# PilotPi_Power.net
KiCad netlist of a schematic drawn in Altium Designer
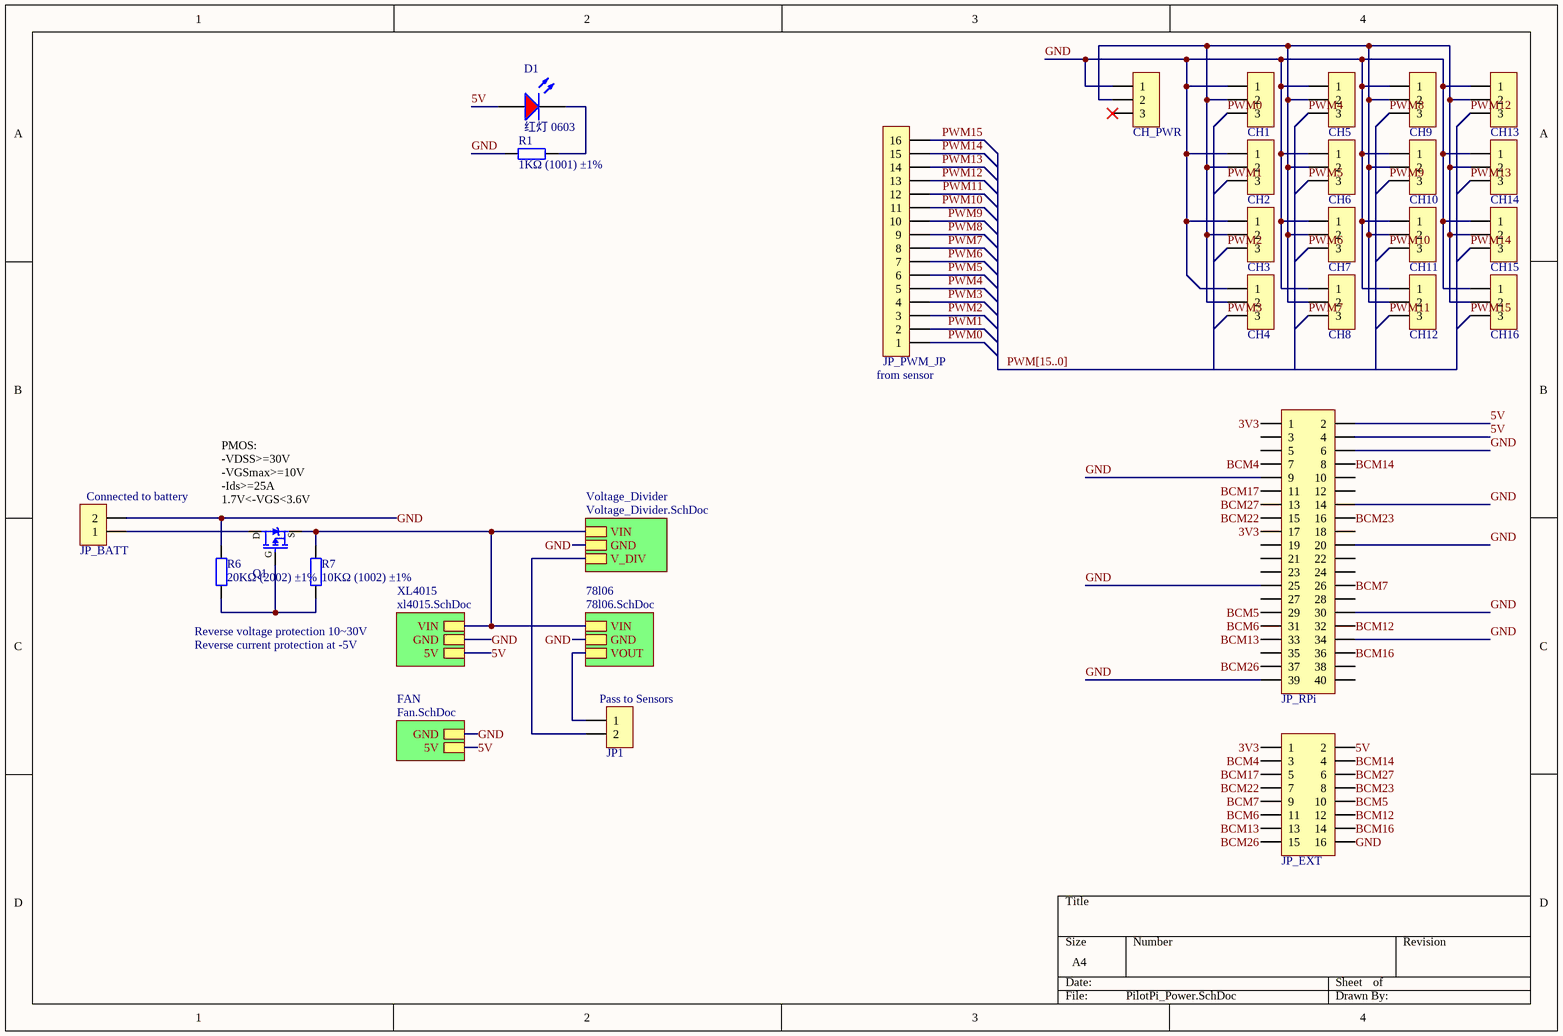
[diagram p0: PilotPi_Power.SchDoc]

(export (version "E")
  (design (tool "Eeschema 10.0.6"))
  (components
    (comp (ref "CH1")
      (value "HDR-1X3")
      (footprint "HDR2.54-LI-3P")
      (description "3P接插件")
      (fields (field (name "版权归属") "源创客"))
      (libsource (lib "4.6   - 接插件-脚距2.54") (part "Header 3"))
    )
    (comp (ref "CH2")
      (value "HDR-1X3")
      (footprint "HDR2.54-LI-3P")
      (description "3P接插件")
      (fields (field (name "版权归属") "源创客"))
      (libsource (lib "4.6   - 接插件-脚距2.54") (part "Header 3"))
    )
    (comp (ref "CH3")
      (value "HDR-1X3")
      (footprint "HDR2.54-LI-3P")
      (description "3P接插件")
      (fields (field (name "版权归属") "源创客"))
      (libsource (lib "4.6   - 接插件-脚距2.54") (part "Header 3"))
    )
    (comp (ref "CH4")
      (value "HDR-1X3")
      (footprint "HDR2.54-LI-3P")
      (description "3P接插件")
      (fields (field (name "版权归属") "源创客"))
      (libsource (lib "4.6   - 接插件-脚距2.54") (part "Header 3"))
    )
    (comp (ref "CH5")
      (value "HDR-1X3")
      (footprint "HDR2.54-LI-3P")
      (description "3P接插件")
      (fields (field (name "版权归属") "源创客"))
      (libsource (lib "4.6   - 接插件-脚距2.54") (part "Header 3"))
    )
    (comp (ref "CH6")
      (value "HDR-1X3")
      (footprint "HDR2.54-LI-3P")
      (description "3P接插件")
      (fields (field (name "版权归属") "源创客"))
      (libsource (lib "4.6   - 接插件-脚距2.54") (part "Header 3"))
    )
    (comp (ref "CH7")
      (value "HDR-1X3")
      (footprint "HDR2.54-LI-3P")
      (description "3P接插件")
      (fields (field (name "版权归属") "源创客"))
      (libsource (lib "4.6   - 接插件-脚距2.54") (part "Header 3"))
    )
    (comp (ref "CH8")
      (value "HDR-1X3")
      (footprint "HDR2.54-LI-3P")
      (description "3P接插件")
      (fields (field (name "版权归属") "源创客"))
      (libsource (lib "4.6   - 接插件-脚距2.54") (part "Header 3"))
    )
    (comp (ref "CH9")
      (value "HDR-1X3")
      (footprint "HDR2.54-LI-3P")
      (description "3P接插件")
      (fields (field (name "版权归属") "源创客"))
      (libsource (lib "4.6   - 接插件-脚距2.54") (part "Header 3"))
    )
    (comp (ref "CH10")
      (value "HDR-1X3")
      (footprint "HDR2.54-LI-3P")
      (description "3P接插件")
      (fields (field (name "版权归属") "源创客"))
      (libsource (lib "4.6   - 接插件-脚距2.54") (part "Header 3"))
    )
    (comp (ref "CH11")
      (value "HDR-1X3")
      (footprint "HDR2.54-LI-3P")
      (description "3P接插件")
      (fields (field (name "版权归属") "源创客"))
      (libsource (lib "4.6   - 接插件-脚距2.54") (part "Header 3"))
    )
    (comp (ref "CH12")
      (value "HDR-1X3")
      (footprint "HDR2.54-LI-3P")
      (description "3P接插件")
      (fields (field (name "版权归属") "源创客"))
      (libsource (lib "4.6   - 接插件-脚距2.54") (part "Header 3"))
    )
    (comp (ref "CH13")
      (value "HDR-1X3")
      (footprint "HDR2.54-LI-3P")
      (description "3P接插件")
      (fields (field (name "版权归属") "源创客"))
      (libsource (lib "4.6   - 接插件-脚距2.54") (part "Header 3"))
    )
    (comp (ref "CH14")
      (value "HDR-1X3")
      (footprint "HDR2.54-LI-3P")
      (description "3P接插件")
      (fields (field (name "版权归属") "源创客"))
      (libsource (lib "4.6   - 接插件-脚距2.54") (part "Header 3"))
    )
    (comp (ref "CH15")
      (value "HDR-1X3")
      (footprint "HDR2.54-LI-3P")
      (description "3P接插件")
      (fields (field (name "版权归属") "源创客"))
      (libsource (lib "4.6   - 接插件-脚距2.54") (part "Header 3"))
    )
    (comp (ref "CH16")
      (value "HDR-1X3")
      (footprint "HDR2.54-LI-3P")
      (description "3P接插件")
      (fields (field (name "版权归属") "源创客"))
      (libsource (lib "4.6   - 接插件-脚距2.54") (part "Header 3"))
    )
    (comp (ref "CH_PWR")
      (value "HDR-1X3")
      (footprint "HDR2.54-LI-3P")
      (description "3P接插件")
      (fields (field (name "版权归属") "源创客"))
      (libsource (lib "4.6   - 接插件-脚距2.54") (part "Header 3"))
    )
    (comp (ref "D1")
      (value "红灯 0603")
      (footprint "0603_LED_S1")
      (description "发光二极管")
      (libsource (lib "Miscellaneous Devices LC") (part "0603 红灯"))
    )
    (comp (ref "JP1")
      (value "HDR-1X2")
      (footprint "HDR2.54-M-LI-2P")
      (description "2P接插件")
      (fields (field (name "版权归属") "源创客"))
      (libsource (lib "4.5   - 接插件-脚距2.54") (part "Header 2"))
    )
    (comp (ref "JP_BATT")
      (value "HDR-1X2")
      (footprint "XH2.54-WI-2P")
      (description "2P接插件")
      (fields (field (name "版权归属") "源创客"))
      (libsource (lib "4.6   - 接插件-脚距2.54") (part "Header 2"))
    )
    (comp (ref "JP_EXT")
      (value "Header 8X2")
      (footprint "HDR2.54-LI-2x8P")
      (description "8*2P接插件")
      (fields (field (name "版权归属") "源创客"))
      (libsource (lib "4.5   - 接插件-脚距2.54") (part "Header 8X2"))
    )
    (comp (ref "JP_PWM_JP")
      (value "HDR-1X16")
      (footprint "HDR2.54-M-LI-16P")
      (description "16P接插件")
      (fields (field (name "版权归属") "源创客"))
      (libsource (lib "4.5   - 接插件-脚距2.54") (part "Header 16"))
    )
    (comp (ref "JP_RPi")
      (value "Header 2X11")
      (footprint "HDR2.54-LI-2x20P")
      (description "20*2P接插件")
      (fields (field (name "版权归属") "源创客"))
      (libsource (lib "4.5   - 接插件-脚距2.54") (part "Header 20X2"))
    )
    (comp (ref "Q1")
      (value "D15P05")
      (footprint "TO252")
      (description "P沟道 50V/15A")
      (fields (field (name "版权归属") "源创客"))
      (libsource (lib "6.1   - 场效应管-可控硅") (part "D15P05"))
    )
    (comp (ref "R1")
      (value "1KΩ (1001) ±1%")
      (footprint "0805_R")
      (description "贴片电阻")
      (libsource (lib "Miscellaneous Devices LC") (part "0805 1KΩ (1001) 1%"))
    )
    (comp (ref "R6")
      (value "20KΩ (2002) ±1%")
      (footprint "0805_R")
      (description "贴片电阻")
      (libsource (lib "Miscellaneous Devices LC") (part "0805 20KΩ (2002) 1%"))
    )
    (comp (ref "R7")
      (value "10KΩ (1002) ±1%")
      (footprint "0805_R")
      (description "贴片电阻")
      (libsource (lib "Miscellaneous Devices LC") (part "0805 10KΩ (1002) 1%"))
    )
  )
  (nets
    (net (code "1") (name "/3V3") (class "Default")
      (node (ref "JP_EXT") (pin "1") (pinfunction "1_1") (pintype "passive"))
      (node (ref "JP_RPi") (pin "1") (pinfunction "1_1") (pintype "passive"))
      (node (ref "JP_RPi") (pin "17") (pinfunction "17_17") (pintype "passive"))
    )
    (net (code "2") (name "/5V") (class "Default")
      (node (ref "D1") (pin "A") (pinfunction "A_A") (pintype "passive"))
      (node (ref "JP_EXT") (pin "2") (pinfunction "2_2") (pintype "passive"))
      (node (ref "JP_RPi") (pin "2") (pinfunction "2_2") (pintype "passive"))
      (node (ref "JP_RPi") (pin "4") (pinfunction "4_4") (pintype "passive"))
    )
    (net (code "3") (name "/BCM4") (class "Default")
      (node (ref "JP_EXT") (pin "3") (pinfunction "3_3") (pintype "passive"))
      (node (ref "JP_RPi") (pin "7") (pinfunction "7_7") (pintype "passive"))
    )
    (net (code "4") (name "/BCM5") (class "Default")
      (node (ref "JP_EXT") (pin "10") (pinfunction "10_10") (pintype "passive"))
      (node (ref "JP_RPi") (pin "29") (pinfunction "29_29") (pintype "passive"))
    )
    (net (code "5") (name "/BCM6") (class "Default")
      (node (ref "JP_EXT") (pin "11") (pinfunction "11_11") (pintype "passive"))
      (node (ref "JP_RPi") (pin "31") (pinfunction "31_31") (pintype "passive"))
    )
    (net (code "6") (name "/BCM7") (class "Default")
      (node (ref "JP_EXT") (pin "9") (pinfunction "9_9") (pintype "passive"))
      (node (ref "JP_RPi") (pin "26") (pinfunction "26_26") (pintype "passive"))
    )
    (net (code "7") (name "/BCM12") (class "Default")
      (node (ref "JP_EXT") (pin "12") (pinfunction "12_12") (pintype "passive"))
      (node (ref "JP_RPi") (pin "32") (pinfunction "32_32") (pintype "passive"))
    )
    (net (code "8") (name "/BCM13") (class "Default")
      (node (ref "JP_EXT") (pin "13") (pinfunction "13_13") (pintype "passive"))
      (node (ref "JP_RPi") (pin "33") (pinfunction "33_33") (pintype "passive"))
    )
    (net (code "9") (name "/BCM14") (class "Default")
      (node (ref "JP_EXT") (pin "4") (pinfunction "4_4") (pintype "passive"))
      (node (ref "JP_RPi") (pin "8") (pinfunction "8_8") (pintype "passive"))
    )
    (net (code "10") (name "/BCM16") (class "Default")
      (node (ref "JP_EXT") (pin "14") (pinfunction "14_14") (pintype "passive"))
      (node (ref "JP_RPi") (pin "36") (pinfunction "36_36") (pintype "passive"))
    )
    (net (code "11") (name "/BCM17") (class "Default")
      (node (ref "JP_EXT") (pin "5") (pinfunction "5_5") (pintype "passive"))
      (node (ref "JP_RPi") (pin "11") (pinfunction "11_11") (pintype "passive"))
    )
    (net (code "12") (name "/BCM22") (class "Default")
      (node (ref "JP_EXT") (pin "7") (pinfunction "7_7") (pintype "passive"))
      (node (ref "JP_RPi") (pin "15") (pinfunction "15_15") (pintype "passive"))
    )
    (net (code "13") (name "/BCM23") (class "Default")
      (node (ref "JP_EXT") (pin "8") (pinfunction "8_8") (pintype "passive"))
      (node (ref "JP_RPi") (pin "16") (pinfunction "16_16") (pintype "passive"))
    )
    (net (code "14") (name "/BCM26") (class "Default")
      (node (ref "JP_EXT") (pin "15") (pinfunction "15_15") (pintype "passive"))
      (node (ref "JP_RPi") (pin "37") (pinfunction "37_37") (pintype "passive"))
    )
    (net (code "15") (name "/BCM27") (class "Default")
      (node (ref "JP_EXT") (pin "6") (pinfunction "6_6") (pintype "passive"))
      (node (ref "JP_RPi") (pin "13") (pinfunction "13_13") (pintype "passive"))
    )
    (net (code "16") (name "/GND") (class "Default")
      (node (ref "CH1") (pin "1") (pinfunction "1_1") (pintype "passive"))
      (node (ref "CH10") (pin "1") (pinfunction "1_1") (pintype "passive"))
      (node (ref "CH11") (pin "1") (pinfunction "1_1") (pintype "passive"))
      (node (ref "CH12") (pin "1") (pinfunction "1_1") (pintype "passive"))
      (node (ref "CH13") (pin "1") (pinfunction "1_1") (pintype "passive"))
      (node (ref "CH14") (pin "1") (pinfunction "1_1") (pintype "passive"))
      (node (ref "CH15") (pin "1") (pinfunction "1_1") (pintype "passive"))
      (node (ref "CH16") (pin "1") (pinfunction "1_1") (pintype "passive"))
      (node (ref "CH2") (pin "1") (pinfunction "1_1") (pintype "passive"))
      (node (ref "CH3") (pin "1") (pinfunction "1_1") (pintype "passive"))
      (node (ref "CH4") (pin "1") (pinfunction "1_1") (pintype "passive"))
      (node (ref "CH5") (pin "1") (pinfunction "1_1") (pintype "passive"))
      (node (ref "CH6") (pin "1") (pinfunction "1_1") (pintype "passive"))
      (node (ref "CH7") (pin "1") (pinfunction "1_1") (pintype "passive"))
      (node (ref "CH8") (pin "1") (pinfunction "1_1") (pintype "passive"))
      (node (ref "CH9") (pin "1") (pinfunction "1_1") (pintype "passive"))
      (node (ref "CH_PWR") (pin "1") (pinfunction "1_1") (pintype "passive"))
      (node (ref "JP_BATT") (pin "2") (pinfunction "2_2") (pintype "power_in"))
      (node (ref "JP_EXT") (pin "16") (pinfunction "16_16") (pintype "passive"))
      (node (ref "JP_RPi") (pin "14") (pinfunction "14_14") (pintype "passive"))
      (node (ref "JP_RPi") (pin "20") (pinfunction "20_20") (pintype "passive"))
      (node (ref "JP_RPi") (pin "25") (pinfunction "25_25") (pintype "passive"))
      (node (ref "JP_RPi") (pin "30") (pinfunction "30_30") (pintype "passive"))
      (node (ref "JP_RPi") (pin "34") (pinfunction "34_34") (pintype "passive"))
      (node (ref "JP_RPi") (pin "39") (pinfunction "39_39") (pintype "passive"))
      (node (ref "JP_RPi") (pin "6") (pinfunction "6_6") (pintype "passive"))
      (node (ref "JP_RPi") (pin "9") (pinfunction "9_9") (pintype "passive"))
      (node (ref "R1") (pin "1") (pinfunction "1_1") (pintype "passive"))
      (node (ref "R6") (pin "2") (pinfunction "2_2") (pintype "passive"))
    )
    (net (code "17") (name "/PWM0") (class "Default")
      (node (ref "CH1") (pin "3") (pinfunction "3_3") (pintype "passive"))
      (node (ref "JP_PWM_JP") (pin "1") (pinfunction "1_1") (pintype "passive"))
    )
    (net (code "18") (name "/PWM1") (class "Default")
      (node (ref "CH2") (pin "3") (pinfunction "3_3") (pintype "passive"))
      (node (ref "JP_PWM_JP") (pin "2") (pinfunction "2_2") (pintype "passive"))
    )
    (net (code "19") (name "/PWM2") (class "Default")
      (node (ref "CH3") (pin "3") (pinfunction "3_3") (pintype "passive"))
      (node (ref "JP_PWM_JP") (pin "3") (pinfunction "3_3") (pintype "passive"))
    )
    (net (code "20") (name "/PWM3") (class "Default")
      (node (ref "CH4") (pin "3") (pinfunction "3_3") (pintype "passive"))
      (node (ref "JP_PWM_JP") (pin "4") (pinfunction "4_4") (pintype "passive"))
    )
    (net (code "21") (name "/PWM4") (class "Default")
      (node (ref "CH5") (pin "3") (pinfunction "3_3") (pintype "passive"))
      (node (ref "JP_PWM_JP") (pin "5") (pinfunction "5_5") (pintype "passive"))
    )
    (net (code "22") (name "/PWM5") (class "Default")
      (node (ref "CH6") (pin "3") (pinfunction "3_3") (pintype "passive"))
      (node (ref "JP_PWM_JP") (pin "6") (pinfunction "6_6") (pintype "passive"))
    )
    (net (code "23") (name "/PWM6") (class "Default")
      (node (ref "CH7") (pin "3") (pinfunction "3_3") (pintype "passive"))
      (node (ref "JP_PWM_JP") (pin "7") (pinfunction "7_7") (pintype "passive"))
    )
    (net (code "24") (name "/PWM7") (class "Default")
      (node (ref "CH8") (pin "3") (pinfunction "3_3") (pintype "passive"))
      (node (ref "JP_PWM_JP") (pin "8") (pinfunction "8_8") (pintype "passive"))
    )
    (net (code "25") (name "/PWM8") (class "Default")
      (node (ref "CH9") (pin "3") (pinfunction "3_3") (pintype "passive"))
      (node (ref "JP_PWM_JP") (pin "9") (pinfunction "9_9") (pintype "passive"))
    )
    (net (code "26") (name "/PWM9") (class "Default")
      (node (ref "CH10") (pin "3") (pinfunction "3_3") (pintype "passive"))
      (node (ref "JP_PWM_JP") (pin "10") (pinfunction "10_10") (pintype "passive"))
    )
    (net (code "27") (name "/PWM10") (class "Default")
      (node (ref "CH11") (pin "3") (pinfunction "3_3") (pintype "passive"))
      (node (ref "JP_PWM_JP") (pin "11") (pinfunction "11_11") (pintype "passive"))
    )
    (net (code "28") (name "/PWM11") (class "Default")
      (node (ref "CH12") (pin "3") (pinfunction "3_3") (pintype "passive"))
      (node (ref "JP_PWM_JP") (pin "12") (pinfunction "12_12") (pintype "passive"))
    )
    (net (code "29") (name "/PWM12") (class "Default")
      (node (ref "CH13") (pin "3") (pinfunction "3_3") (pintype "passive"))
      (node (ref "JP_PWM_JP") (pin "13") (pinfunction "13_13") (pintype "passive"))
    )
    (net (code "30") (name "/PWM13") (class "Default")
      (node (ref "CH14") (pin "3") (pinfunction "3_3") (pintype "passive"))
      (node (ref "JP_PWM_JP") (pin "14") (pinfunction "14_14") (pintype "passive"))
    )
    (net (code "31") (name "/PWM14") (class "Default")
      (node (ref "CH15") (pin "3") (pinfunction "3_3") (pintype "passive"))
      (node (ref "JP_PWM_JP") (pin "15") (pinfunction "15_15") (pintype "passive"))
    )
    (net (code "32") (name "/PWM15") (class "Default")
      (node (ref "CH16") (pin "3") (pinfunction "3_3") (pintype "passive"))
      (node (ref "JP_PWM_JP") (pin "16") (pinfunction "16_16") (pintype "passive"))
    )
    (net (code "34") (name "/VIN") (class "Default")
      (node (ref "Q1") (pin "3") (pinfunction "D_3") (pintype "passive"))
      (node (ref "R7") (pin "2") (pinfunction "2_2") (pintype "passive"))
    )
    (net (code "35") (name "/VOUT") (class "Default")
      (node (ref "JP1") (pin "1") (pinfunction "1_1") (pintype "passive"))
    )
    (net (code "36") (name "/V_DIV") (class "Default")
      (node (ref "JP1") (pin "2") (pinfunction "2_2") (pintype "passive"))
    )
    (net (code "37") (name "Net-(CH1-Pad2)") (class "Default")
      (node (ref "CH1") (pin "2") (pinfunction "2_2") (pintype "passive"))
      (node (ref "CH10") (pin "2") (pinfunction "2_2") (pintype "passive"))
      (node (ref "CH11") (pin "2") (pinfunction "2_2") (pintype "passive"))
      (node (ref "CH12") (pin "2") (pinfunction "2_2") (pintype "passive"))
      (node (ref "CH13") (pin "2") (pinfunction "2_2") (pintype "passive"))
      (node (ref "CH14") (pin "2") (pinfunction "2_2") (pintype "passive"))
      (node (ref "CH15") (pin "2") (pinfunction "2_2") (pintype "passive"))
      (node (ref "CH16") (pin "2") (pinfunction "2_2") (pintype "passive"))
      (node (ref "CH2") (pin "2") (pinfunction "2_2") (pintype "passive"))
      (node (ref "CH3") (pin "2") (pinfunction "2_2") (pintype "passive"))
      (node (ref "CH4") (pin "2") (pinfunction "2_2") (pintype "passive"))
      (node (ref "CH5") (pin "2") (pinfunction "2_2") (pintype "passive"))
      (node (ref "CH6") (pin "2") (pinfunction "2_2") (pintype "passive"))
      (node (ref "CH7") (pin "2") (pinfunction "2_2") (pintype "passive"))
      (node (ref "CH8") (pin "2") (pinfunction "2_2") (pintype "passive"))
      (node (ref "CH9") (pin "2") (pinfunction "2_2") (pintype "passive"))
      (node (ref "CH_PWR") (pin "2") (pinfunction "2_2") (pintype "passive"))
    )
    (net (code "38") (name "Net-(D1-PadK)") (class "Default")
      (node (ref "D1") (pin "K") (pinfunction "K_K") (pintype "passive"))
      (node (ref "R1") (pin "2") (pinfunction "2_2") (pintype "passive"))
    )
    (net (code "39") (name "Net-(Q1-G)") (class "Default")
      (node (ref "Q1") (pin "1") (pinfunction "G_1") (pintype "passive"))
      (node (ref "R6") (pin "1") (pinfunction "1_1") (pintype "passive"))
      (node (ref "R7") (pin "1") (pinfunction "1_1") (pintype "passive"))
    )
    (net (code "40") (name "Net-(Q1-S)") (class "Default")
      (node (ref "JP_BATT") (pin "1") (pinfunction "1_1") (pintype "power_in"))
      (node (ref "Q1") (pin "2") (pinfunction "S_2") (pintype "passive"))
    )
    (net (code "41") (name "unconnected-(CH_PWR-Pad3)") (class "Default")
      (node (ref "CH_PWR") (pin "3") (pinfunction "3_3") (pintype "passive+no_connect"))
    )
    (net (code "42") (name "unconnected-(JP_RPi-Pad3)") (class "Default")
      (node (ref "JP_RPi") (pin "3") (pinfunction "3_3") (pintype "passive"))
    )
    (net (code "43") (name "unconnected-(JP_RPi-Pad5)") (class "Default")
      (node (ref "JP_RPi") (pin "5") (pinfunction "5_5") (pintype "passive"))
    )
    (net (code "44") (name "unconnected-(JP_RPi-Pad10)") (class "Default")
      (node (ref "JP_RPi") (pin "10") (pinfunction "10_10") (pintype "passive"))
    )
    (net (code "45") (name "unconnected-(JP_RPi-Pad12)") (class "Default")
      (node (ref "JP_RPi") (pin "12") (pinfunction "12_12") (pintype "passive"))
    )
    (net (code "46") (name "unconnected-(JP_RPi-Pad18)") (class "Default")
      (node (ref "JP_RPi") (pin "18") (pinfunction "18_18") (pintype "passive"))
    )
    (net (code "47") (name "unconnected-(JP_RPi-Pad19)") (class "Default")
      (node (ref "JP_RPi") (pin "19") (pinfunction "19_19") (pintype "passive"))
    )
    (net (code "48") (name "unconnected-(JP_RPi-Pad21)") (class "Default")
      (node (ref "JP_RPi") (pin "21") (pinfunction "21_21") (pintype "passive"))
    )
    (net (code "49") (name "unconnected-(JP_RPi-Pad22)") (class "Default")
      (node (ref "JP_RPi") (pin "22") (pinfunction "22_22") (pintype "passive"))
    )
    (net (code "50") (name "unconnected-(JP_RPi-Pad23)") (class "Default")
      (node (ref "JP_RPi") (pin "23") (pinfunction "23_23") (pintype "passive"))
    )
    (net (code "51") (name "unconnected-(JP_RPi-Pad24)") (class "Default")
      (node (ref "JP_RPi") (pin "24") (pinfunction "24_24") (pintype "passive"))
    )
    (net (code "52") (name "unconnected-(JP_RPi-Pad27)") (class "Default")
      (node (ref "JP_RPi") (pin "27") (pinfunction "27_27") (pintype "passive"))
    )
    (net (code "53") (name "unconnected-(JP_RPi-Pad28)") (class "Default")
      (node (ref "JP_RPi") (pin "28") (pinfunction "28_28") (pintype "passive"))
    )
    (net (code "54") (name "unconnected-(JP_RPi-Pad35)") (class "Default")
      (node (ref "JP_RPi") (pin "35") (pinfunction "35_35") (pintype "passive"))
    )
    (net (code "55") (name "unconnected-(JP_RPi-Pad38)") (class "Default")
      (node (ref "JP_RPi") (pin "38") (pinfunction "38_38") (pintype "passive"))
    )
    (net (code "56") (name "unconnected-(JP_RPi-Pad40)") (class "Default")
      (node (ref "JP_RPi") (pin "40") (pinfunction "40_40") (pintype "passive"))
    )
  )
)
